# HZX_Board.net
KiCad netlist of a schematic drawn in EAGLE
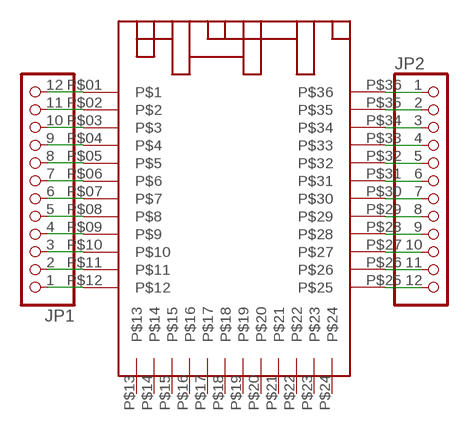
[diagram p0: schematic, sheet 1]

(export (version "E")
  (design (tool "Eeschema 10.0.6"))
  (components
    (comp (ref "JP1")
      (value "PINHD-1X12")
      (footprint "eagle-import:1X12")
      (libsource (lib "eagle-import") (part "PINHD-1X12"))
    )
    (comp (ref "JP2")
      (value "PINHD-1X12")
      (footprint "eagle-import:1X12")
      (libsource (lib "eagle-import") (part "PINHD-1X12"))
    )
    (comp (ref "U$1")
      (value "HZX_MODULE")
      (footprint "eagle-import:SMD_PAD_VERSION")
      (fields (field (name "AUTHOR") "Agam"))
      (libsource (lib "eagle-import") (part "HZX_MODULE"))
    )
  )
  (nets
    (net (code "1") (name "Net-(JP1-Pad1)") (class "Default")
      (node (ref "JP1") (pin "1") (pinfunction "1_1") (pintype "passive"))
      (node (ref "U$1") (pin "P$12") (pinfunction "P$12_P$12") (pintype "bidirectional"))
    )
    (net (code "2") (name "Net-(JP1-Pad2)") (class "Default")
      (node (ref "JP1") (pin "2") (pinfunction "2_2") (pintype "passive"))
      (node (ref "U$1") (pin "P$11") (pinfunction "P$11_P$11") (pintype "bidirectional"))
    )
    (net (code "3") (name "Net-(JP1-Pad3)") (class "Default")
      (node (ref "JP1") (pin "3") (pinfunction "3_3") (pintype "passive"))
      (node (ref "U$1") (pin "P$10") (pinfunction "P$10_P$10") (pintype "bidirectional"))
    )
    (net (code "4") (name "Net-(JP2-Pad1)") (class "Default")
      (node (ref "JP2") (pin "1") (pinfunction "1_1") (pintype "passive"))
      (node (ref "U$1") (pin "P$36") (pinfunction "P$36_P$36") (pintype "bidirectional"))
    )
    (net (code "5") (name "Net-(JP2-Pad2)") (class "Default")
      (node (ref "JP2") (pin "2") (pinfunction "2_2") (pintype "passive"))
      (node (ref "U$1") (pin "P$35") (pinfunction "P$35_P$35") (pintype "bidirectional"))
    )
    (net (code "6") (name "Net-(JP2-Pad3)") (class "Default")
      (node (ref "JP2") (pin "3") (pinfunction "3_3") (pintype "passive"))
      (node (ref "U$1") (pin "P$34") (pinfunction "P$34_P$34") (pintype "bidirectional"))
    )
    (net (code "7") (name "Net-(JP2-Pad4)") (class "Default")
      (node (ref "JP2") (pin "4") (pinfunction "4_4") (pintype "passive"))
      (node (ref "U$1") (pin "P$33") (pinfunction "P$33_P$33") (pintype "bidirectional"))
    )
    (net (code "8") (name "Net-(JP2-Pad5)") (class "Default")
      (node (ref "JP2") (pin "5") (pinfunction "5_5") (pintype "passive"))
      (node (ref "U$1") (pin "P$32") (pinfunction "P$32_P$32") (pintype "bidirectional"))
    )
    (net (code "9") (name "Net-(JP2-Pad6)") (class "Default")
      (node (ref "JP2") (pin "6") (pinfunction "6_6") (pintype "passive"))
      (node (ref "U$1") (pin "P$31") (pinfunction "P$31_P$31") (pintype "bidirectional"))
    )
    (net (code "10") (name "Net-(JP2-Pad7)") (class "Default")
      (node (ref "JP2") (pin "7") (pinfunction "7_7") (pintype "passive"))
      (node (ref "U$1") (pin "P$30") (pinfunction "P$30_P$30") (pintype "bidirectional"))
    )
    (net (code "11") (name "Net-(JP2-Pad8)") (class "Default")
      (node (ref "JP2") (pin "8") (pinfunction "8_8") (pintype "passive"))
      (node (ref "U$1") (pin "P$29") (pinfunction "P$29_P$29") (pintype "bidirectional"))
    )
    (net (code "12") (name "Net-(JP2-Pad9)") (class "Default")
      (node (ref "JP2") (pin "9") (pinfunction "9_9") (pintype "passive"))
      (node (ref "U$1") (pin "P$28") (pinfunction "P$28_P$28") (pintype "bidirectional"))
    )
    (net (code "13") (name "Net-(JP2-Pad10)") (class "Default")
      (node (ref "JP2") (pin "10") (pinfunction "10_10") (pintype "passive"))
      (node (ref "U$1") (pin "P$27") (pinfunction "P$27_P$27") (pintype "bidirectional"))
    )
    (net (code "14") (name "Net-(JP2-Pad11)") (class "Default")
      (node (ref "JP2") (pin "11") (pinfunction "11_11") (pintype "passive"))
      (node (ref "U$1") (pin "P$26") (pinfunction "P$26_P$26") (pintype "bidirectional"))
    )
    (net (code "15") (name "Net-(JP2-Pad12)") (class "Default")
      (node (ref "JP2") (pin "12") (pinfunction "12_12") (pintype "passive"))
      (node (ref "U$1") (pin "P$25") (pinfunction "P$25_P$25") (pintype "bidirectional"))
    )
    (net (code "16") (name "Net-(U$1-P$1)") (class "Default")
      (node (ref "JP1") (pin "12") (pinfunction "12_12") (pintype "passive"))
      (node (ref "U$1") (pin "P$01") (pinfunction "P$1_P$01") (pintype "bidirectional"))
    )
    (net (code "17") (name "Net-(U$1-P$2)") (class "Default")
      (node (ref "JP1") (pin "11") (pinfunction "11_11") (pintype "passive"))
      (node (ref "U$1") (pin "P$02") (pinfunction "P$2_P$02") (pintype "bidirectional"))
    )
    (net (code "18") (name "Net-(U$1-P$3)") (class "Default")
      (node (ref "JP1") (pin "10") (pinfunction "10_10") (pintype "passive"))
      (node (ref "U$1") (pin "P$03") (pinfunction "P$3_P$03") (pintype "bidirectional"))
    )
    (net (code "19") (name "Net-(U$1-P$4)") (class "Default")
      (node (ref "JP1") (pin "9") (pinfunction "9_9") (pintype "passive"))
      (node (ref "U$1") (pin "P$04") (pinfunction "P$4_P$04") (pintype "bidirectional"))
    )
    (net (code "20") (name "Net-(U$1-P$5)") (class "Default")
      (node (ref "JP1") (pin "8") (pinfunction "8_8") (pintype "passive"))
      (node (ref "U$1") (pin "P$05") (pinfunction "P$5_P$05") (pintype "bidirectional"))
    )
    (net (code "21") (name "Net-(U$1-P$6)") (class "Default")
      (node (ref "JP1") (pin "7") (pinfunction "7_7") (pintype "passive"))
      (node (ref "U$1") (pin "P$06") (pinfunction "P$6_P$06") (pintype "bidirectional"))
    )
    (net (code "22") (name "Net-(U$1-P$7)") (class "Default")
      (node (ref "JP1") (pin "6") (pinfunction "6_6") (pintype "passive"))
      (node (ref "U$1") (pin "P$07") (pinfunction "P$7_P$07") (pintype "bidirectional"))
    )
    (net (code "23") (name "Net-(U$1-P$8)") (class "Default")
      (node (ref "JP1") (pin "5") (pinfunction "5_5") (pintype "passive"))
      (node (ref "U$1") (pin "P$08") (pinfunction "P$8_P$08") (pintype "bidirectional"))
    )
    (net (code "24") (name "Net-(U$1-P$9)") (class "Default")
      (node (ref "JP1") (pin "4") (pinfunction "4_4") (pintype "passive"))
      (node (ref "U$1") (pin "P$09") (pinfunction "P$9_P$09") (pintype "bidirectional"))
    )
    (net (code "25") (name "unconnected-(U$1-PadP$13)") (class "Default")
      (node (ref "U$1") (pin "P$13") (pinfunction "P$13_P$13") (pintype "bidirectional"))
    )
    (net (code "26") (name "unconnected-(U$1-PadP$14)") (class "Default")
      (node (ref "U$1") (pin "P$14") (pinfunction "P$14_P$14") (pintype "bidirectional"))
    )
    (net (code "27") (name "unconnected-(U$1-PadP$15)") (class "Default")
      (node (ref "U$1") (pin "P$15") (pinfunction "P$15_P$15") (pintype "bidirectional"))
    )
    (net (code "28") (name "unconnected-(U$1-PadP$16)") (class "Default")
      (node (ref "U$1") (pin "P$16") (pinfunction "P$16_P$16") (pintype "bidirectional"))
    )
    (net (code "29") (name "unconnected-(U$1-PadP$17)") (class "Default")
      (node (ref "U$1") (pin "P$17") (pinfunction "P$17_P$17") (pintype "bidirectional"))
    )
    (net (code "30") (name "unconnected-(U$1-PadP$18)") (class "Default")
      (node (ref "U$1") (pin "P$18") (pinfunction "P$18_P$18") (pintype "bidirectional"))
    )
    (net (code "31") (name "unconnected-(U$1-PadP$19)") (class "Default")
      (node (ref "U$1") (pin "P$19") (pinfunction "P$19_P$19") (pintype "bidirectional"))
    )
    (net (code "32") (name "unconnected-(U$1-PadP$20)") (class "Default")
      (node (ref "U$1") (pin "P$20") (pinfunction "P$20_P$20") (pintype "bidirectional"))
    )
    (net (code "33") (name "unconnected-(U$1-PadP$21)") (class "Default")
      (node (ref "U$1") (pin "P$21") (pinfunction "P$21_P$21") (pintype "bidirectional"))
    )
    (net (code "34") (name "unconnected-(U$1-PadP$22)") (class "Default")
      (node (ref "U$1") (pin "P$22") (pinfunction "P$22_P$22") (pintype "bidirectional"))
    )
    (net (code "35") (name "unconnected-(U$1-PadP$23)") (class "Default")
      (node (ref "U$1") (pin "P$23") (pinfunction "P$23_P$23") (pintype "bidirectional"))
    )
    (net (code "36") (name "unconnected-(U$1-PadP$24)") (class "Default")
      (node (ref "U$1") (pin "P$24") (pinfunction "P$24_P$24") (pintype "bidirectional"))
    )
  )
)
